# hw2.net
KiCad netlist of a schematic drawn in EAGLE
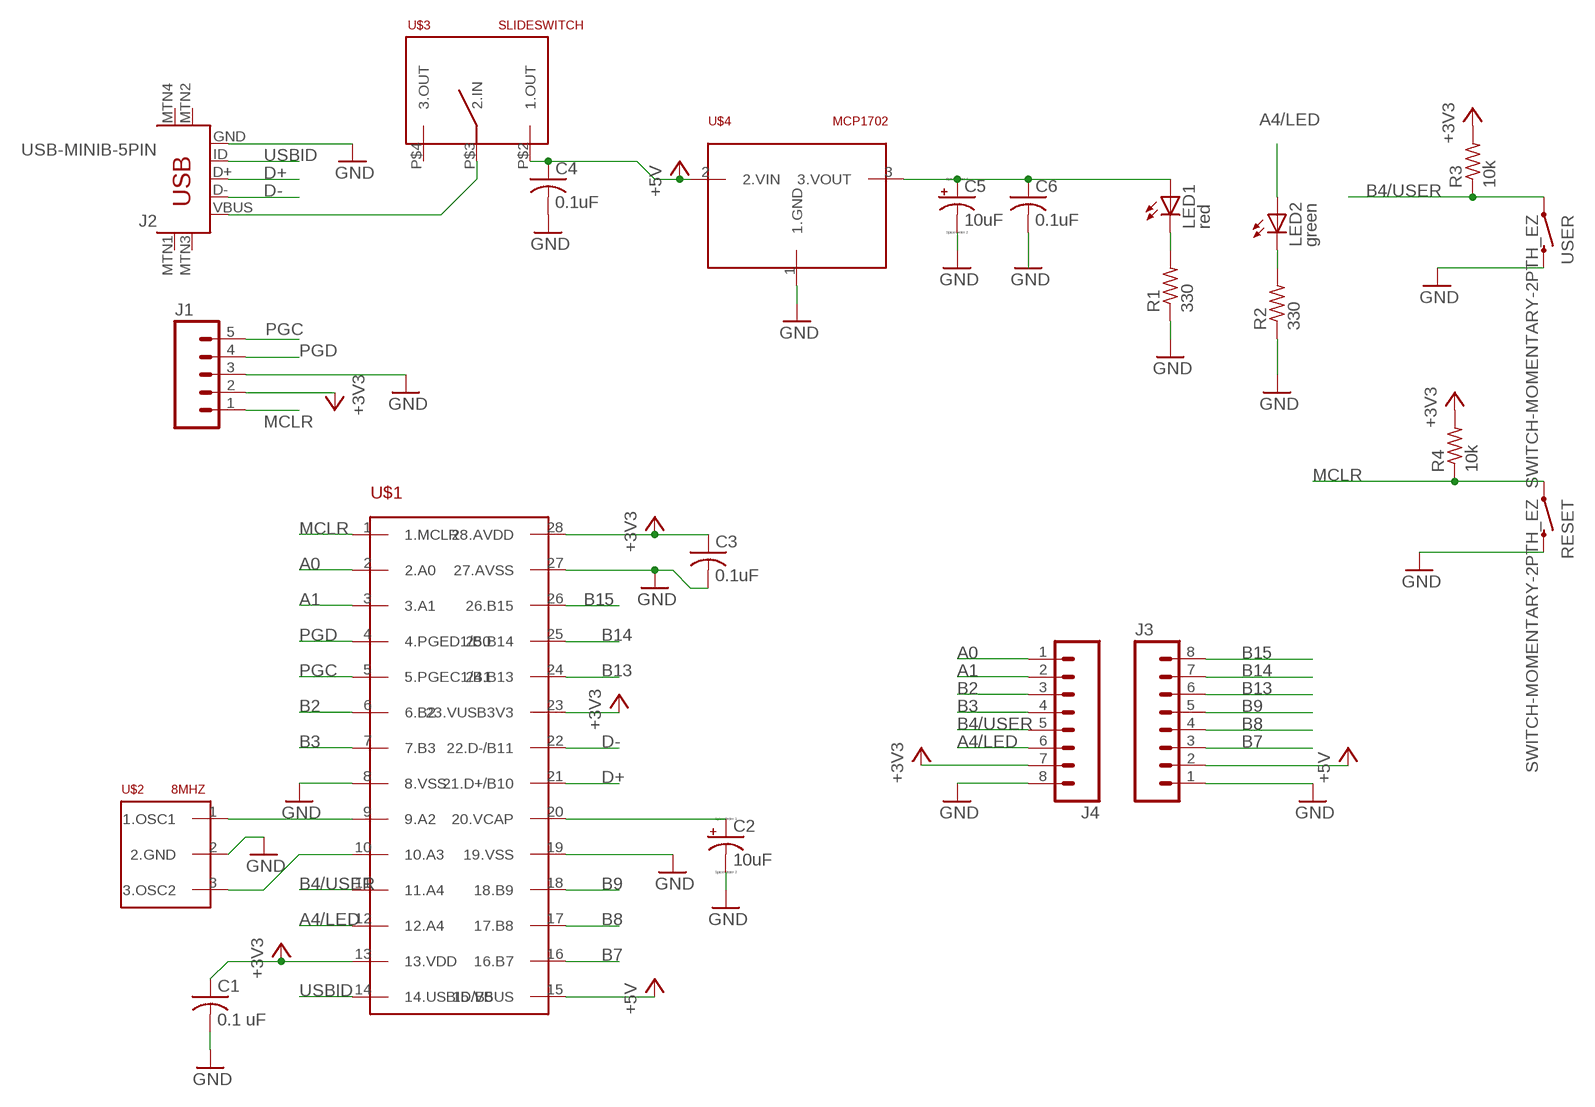
[diagram p0: schematic, sheet 1]

(export (version "E")
  (design (tool "Eeschema 10.0.6"))
  (components
    (comp (ref "C1")
      (value "0.1 uF")
      (footprint "eagle-import:C025-024X044")
      (libsource (lib "eagle-import") (part "C-US025-024X044"))
    )
    (comp (ref "C2")
      (value "10uF")
      (footprint "eagle-import:085CS_1AR")
      (libsource (lib "eagle-import") (part "CPOL-US085CS-1AR"))
    )
    (comp (ref "C3")
      (value "0.1uF")
      (footprint "eagle-import:C025-024X044")
      (libsource (lib "eagle-import") (part "C-US025-024X044"))
    )
    (comp (ref "C4")
      (value "0.1uF")
      (footprint "eagle-import:C025-024X044")
      (libsource (lib "eagle-import") (part "C-US025-024X044"))
    )
    (comp (ref "C5")
      (value "10uF")
      (footprint "eagle-import:085CS_1AR")
      (libsource (lib "eagle-import") (part "CPOL-US085CS-1AR"))
    )
    (comp (ref "C6")
      (value "0.1uF")
      (footprint "eagle-import:C025-024X044")
      (libsource (lib "eagle-import") (part "C-US025-024X044"))
    )
    (comp (ref "J1")
      (value "M05PTH")
      (footprint "eagle-import:1X05")
      (libsource (lib "eagle-import") (part "M05PTH"))
    )
    (comp (ref "J2")
      (value "USB-MINIB-5PIN")
      (footprint "eagle-import:USB-MINIB")
      (libsource (lib "eagle-import") (part "USB-MINIB-5PIN"))
    )
    (comp (ref "J3")
      (value "M08")
      (footprint "eagle-import:1X08_ROUND")
      (libsource (lib "eagle-import") (part "M08"))
    )
    (comp (ref "J4")
      (value "M08")
      (footprint "eagle-import:1X08_ROUND")
      (libsource (lib "eagle-import") (part "M08"))
    )
    (comp (ref "LED1")
      (value "red")
      (footprint "eagle-import:LED3MM")
      (libsource (lib "eagle-import") (part "LED3MM"))
    )
    (comp (ref "LED2")
      (value "green")
      (footprint "eagle-import:LED3MM")
      (libsource (lib "eagle-import") (part "LED3MM"))
    )
    (comp (ref "R1")
      (value "330")
      (footprint "eagle-import:0207_10")
      (libsource (lib "eagle-import") (part "R-US_0207/10"))
    )
    (comp (ref "R2")
      (value "330")
      (footprint "eagle-import:0207_10")
      (libsource (lib "eagle-import") (part "R-US_0207/10"))
    )
    (comp (ref "R3")
      (value "10k")
      (footprint "eagle-import:0207_10")
      (libsource (lib "eagle-import") (part "R-US_0207/10"))
    )
    (comp (ref "R4")
      (value "10k")
      (footprint "eagle-import:0207_10")
      (libsource (lib "eagle-import") (part "R-US_0207/10"))
    )
    (comp (ref "RESET")
      (value "SWITCH-MOMENTARY-2PTH_EZ")
      (footprint "eagle-import:TACTILE-PTH-EZ")
      (libsource (lib "eagle-import") (part "SWITCH-MOMENTARY-2PTH_EZ"))
    )
    (comp (ref "U$1")
      (value "PIC32MX250F128B")
      (footprint "eagle-import:DIL28-3")
      (libsource (lib "eagle-import") (part "PIC32MX250F128B"))
    )
    (comp (ref "U$2")
      (value "8MHZ")
      (footprint "eagle-import:RESONATOR-PTH")
      (libsource (lib "eagle-import") (part "8MHZ"))
    )
    (comp (ref "U$3")
      (value "SLIDESWITCH")
      (footprint "eagle-import:SLIDESWITCH")
      (libsource (lib "eagle-import") (part "SLIDESWITCH"))
    )
    (comp (ref "U$4")
      (value "MCP1702")
      (footprint "eagle-import:TO92")
      (libsource (lib "eagle-import") (part "MCP1702"))
    )
    (comp (ref "USER")
      (value "SWITCH-MOMENTARY-2PTH_EZ")
      (footprint "eagle-import:TACTILE-PTH-EZ")
      (libsource (lib "eagle-import") (part "SWITCH-MOMENTARY-2PTH_EZ"))
    )
  )
  (nets
    (net (code "1") (name "+3V3") (class "Default")
      (node (ref "C1") (pin "1") (pinfunction "1_1") (pintype "passive"))
      (node (ref "C3") (pin "1") (pinfunction "1_1") (pintype "passive"))
      (node (ref "J1") (pin "2") (pinfunction "2_2") (pintype "passive"))
      (node (ref "J4") (pin "7") (pinfunction "7_7") (pintype "passive"))
      (node (ref "R3") (pin "2") (pinfunction "2_2") (pintype "passive"))
      (node (ref "R4") (pin "2") (pinfunction "2_2") (pintype "passive"))
      (node (ref "U$1") (pin "13") (pinfunction "13.VDD_13") (pintype "bidirectional"))
      (node (ref "U$1") (pin "23") (pinfunction "23.VUSB3V3_23") (pintype "bidirectional"))
      (node (ref "U$1") (pin "28") (pinfunction "28.AVDD_28") (pintype "bidirectional"))
    )
    (net (code "2") (name "+5V") (class "Default")
      (node (ref "C4") (pin "1") (pinfunction "1_1") (pintype "passive"))
      (node (ref "J3") (pin "2") (pinfunction "2_2") (pintype "passive"))
      (node (ref "U$1") (pin "15") (pinfunction "15.VBUS_15") (pintype "bidirectional"))
      (node (ref "U$3") (pin "P$2") (pinfunction "1.OUT_P$2") (pintype "bidirectional"))
      (node (ref "U$4") (pin "2") (pinfunction "2.VIN_2") (pintype "bidirectional"))
    )
    (net (code "3") (name "/A0") (class "Default")
      (node (ref "J4") (pin "1") (pinfunction "1_1") (pintype "passive"))
      (node (ref "U$1") (pin "2") (pinfunction "2.A0_2") (pintype "bidirectional"))
    )
    (net (code "4") (name "/A1") (class "Default")
      (node (ref "J4") (pin "2") (pinfunction "2_2") (pintype "passive"))
      (node (ref "U$1") (pin "3") (pinfunction "3.A1_3") (pintype "bidirectional"))
    )
    (net (code "5") (name "/A4{slash}LED") (class "Default")
      (node (ref "J4") (pin "6") (pinfunction "6_6") (pintype "passive"))
      (node (ref "LED2") (pin "A") (pinfunction "A_A") (pintype "passive"))
      (node (ref "U$1") (pin "12") (pinfunction "12.A4_12") (pintype "bidirectional"))
    )
    (net (code "6") (name "/B2") (class "Default")
      (node (ref "J4") (pin "3") (pinfunction "3_3") (pintype "passive"))
      (node (ref "U$1") (pin "6") (pinfunction "6.B2_6") (pintype "bidirectional"))
    )
    (net (code "7") (name "/B3") (class "Default")
      (node (ref "J4") (pin "4") (pinfunction "4_4") (pintype "passive"))
      (node (ref "U$1") (pin "7") (pinfunction "7.B3_7") (pintype "bidirectional"))
    )
    (net (code "8") (name "/B4{slash}USER") (class "Default")
      (node (ref "J4") (pin "5") (pinfunction "5_5") (pintype "passive"))
      (node (ref "R3") (pin "1") (pinfunction "1_1") (pintype "passive"))
      (node (ref "U$1") (pin "11") (pinfunction "11.A4_11") (pintype "bidirectional"))
      (node (ref "USER") (pin "1") (pinfunction "1_1") (pintype "passive"))
    )
    (net (code "9") (name "/B7") (class "Default")
      (node (ref "J3") (pin "3") (pinfunction "3_3") (pintype "passive"))
      (node (ref "U$1") (pin "16") (pinfunction "16.B7_16") (pintype "bidirectional"))
    )
    (net (code "10") (name "/B8") (class "Default")
      (node (ref "J3") (pin "4") (pinfunction "4_4") (pintype "passive"))
      (node (ref "U$1") (pin "17") (pinfunction "17.B8_17") (pintype "bidirectional"))
    )
    (net (code "11") (name "/B9") (class "Default")
      (node (ref "J3") (pin "5") (pinfunction "5_5") (pintype "passive"))
      (node (ref "U$1") (pin "18") (pinfunction "18.B9_18") (pintype "bidirectional"))
    )
    (net (code "12") (name "/B13") (class "Default")
      (node (ref "J3") (pin "6") (pinfunction "6_6") (pintype "passive"))
      (node (ref "U$1") (pin "24") (pinfunction "24.B13_24") (pintype "bidirectional"))
    )
    (net (code "13") (name "/B14") (class "Default")
      (node (ref "J3") (pin "7") (pinfunction "7_7") (pintype "passive"))
      (node (ref "U$1") (pin "25") (pinfunction "25.B14_25") (pintype "bidirectional"))
    )
    (net (code "14") (name "/B15") (class "Default")
      (node (ref "J3") (pin "8") (pinfunction "8_8") (pintype "passive"))
      (node (ref "U$1") (pin "26") (pinfunction "26.B15_26") (pintype "bidirectional"))
    )
    (net (code "15") (name "/D+") (class "Default")
      (node (ref "J2") (pin "D+") (pinfunction "D+_D+") (pintype "bidirectional"))
      (node (ref "U$1") (pin "21") (pinfunction "21.D+/B10_21") (pintype "bidirectional"))
    )
    (net (code "16") (name "/D-") (class "Default")
      (node (ref "J2") (pin "D-") (pinfunction "D-_D-") (pintype "bidirectional"))
      (node (ref "U$1") (pin "22") (pinfunction "22.D-/B11_22") (pintype "bidirectional"))
    )
    (net (code "17") (name "/MCLR") (class "Default")
      (node (ref "J1") (pin "1") (pinfunction "1_1") (pintype "passive"))
      (node (ref "R4") (pin "1") (pinfunction "1_1") (pintype "passive"))
      (node (ref "RESET") (pin "1") (pinfunction "1_1") (pintype "passive"))
      (node (ref "U$1") (pin "1") (pinfunction "1.MCLR_1") (pintype "bidirectional"))
    )
    (net (code "18") (name "/PGC") (class "Default")
      (node (ref "J1") (pin "5") (pinfunction "5_5") (pintype "passive"))
      (node (ref "U$1") (pin "5") (pinfunction "5.PGEC1/B1_5") (pintype "bidirectional"))
    )
    (net (code "19") (name "/PGD") (class "Default")
      (node (ref "J1") (pin "4") (pinfunction "4_4") (pintype "passive"))
      (node (ref "U$1") (pin "4") (pinfunction "4.PGED1/B0_4") (pintype "bidirectional"))
    )
    (net (code "20") (name "/USBID") (class "Default")
      (node (ref "J2") (pin "ID") (pinfunction "ID_ID") (pintype "bidirectional"))
      (node (ref "U$1") (pin "14") (pinfunction "14.USBID/B5_14") (pintype "bidirectional"))
    )
    (net (code "21") (name "GND") (class "Default")
      (node (ref "C1") (pin "2") (pinfunction "2_2") (pintype "passive"))
      (node (ref "C2") (pin "-") (pinfunction "-_-") (pintype "passive"))
      (node (ref "C3") (pin "2") (pinfunction "2_2") (pintype "passive"))
      (node (ref "C4") (pin "2") (pinfunction "2_2") (pintype "passive"))
      (node (ref "C5") (pin "-") (pinfunction "-_-") (pintype "passive"))
      (node (ref "J1") (pin "3") (pinfunction "3_3") (pintype "passive"))
      (node (ref "J2") (pin "GND") (pinfunction "GND_GND") (pintype "bidirectional"))
      (node (ref "J3") (pin "1") (pinfunction "1_1") (pintype "passive"))
      (node (ref "J4") (pin "8") (pinfunction "8_8") (pintype "passive"))
      (node (ref "R1") (pin "1") (pinfunction "1_1") (pintype "passive"))
      (node (ref "R2") (pin "1") (pinfunction "1_1") (pintype "passive"))
      (node (ref "RESET") (pin "3") (pinfunction "2_3") (pintype "passive"))
      (node (ref "U$1") (pin "19") (pinfunction "19.VSS_19") (pintype "bidirectional"))
      (node (ref "U$1") (pin "27") (pinfunction "27.AVSS_27") (pintype "bidirectional"))
      (node (ref "U$1") (pin "8") (pinfunction "8.VSS_8") (pintype "bidirectional"))
      (node (ref "U$2") (pin "2") (pinfunction "2.GND_2") (pintype "bidirectional"))
      (node (ref "U$4") (pin "1") (pinfunction "1.GND_1") (pintype "bidirectional"))
      (node (ref "USER") (pin "3") (pinfunction "2_3") (pintype "passive"))
    )
    (net (code "22") (name "Net-(LED1-C)") (class "Default")
      (node (ref "LED1") (pin "K") (pinfunction "C_K") (pintype "passive"))
      (node (ref "R1") (pin "2") (pinfunction "2_2") (pintype "passive"))
    )
    (net (code "23") (name "Net-(LED2-C)") (class "Default")
      (node (ref "LED2") (pin "K") (pinfunction "C_K") (pintype "passive"))
      (node (ref "R2") (pin "2") (pinfunction "2_2") (pintype "passive"))
    )
    (net (code "24") (name "Net-(U$1-9.A2)") (class "Default")
      (node (ref "U$1") (pin "9") (pinfunction "9.A2_9") (pintype "bidirectional"))
      (node (ref "U$2") (pin "1") (pinfunction "1.OSC1_1") (pintype "bidirectional"))
    )
    (net (code "25") (name "Net-(U$1-10.A3)") (class "Default")
      (node (ref "U$1") (pin "10") (pinfunction "10.A3_10") (pintype "bidirectional"))
      (node (ref "U$2") (pin "3") (pinfunction "3.OSC2_3") (pintype "bidirectional"))
    )
    (net (code "26") (name "Net-(U$1-20.VCAP)") (class "Default")
      (node (ref "C2") (pin "+") (pinfunction "+_+") (pintype "passive"))
      (node (ref "U$1") (pin "20") (pinfunction "20.VCAP_20") (pintype "bidirectional"))
    )
    (net (code "27") (name "Net-(U$3-2.IN)") (class "Default")
      (node (ref "J2") (pin "VBUS") (pinfunction "VBUS_VBUS") (pintype "bidirectional"))
      (node (ref "U$3") (pin "P$3") (pinfunction "2.IN_P$3") (pintype "bidirectional"))
    )
    (net (code "28") (name "Net-(U$4-3.VOUT)") (class "Default")
      (node (ref "C5") (pin "+") (pinfunction "+_+") (pintype "passive"))
      (node (ref "C6") (pin "1") (pinfunction "1_1") (pintype "passive"))
      (node (ref "LED1") (pin "A") (pinfunction "A_A") (pintype "passive"))
      (node (ref "U$4") (pin "3") (pinfunction "3.VOUT_3") (pintype "bidirectional"))
    )
    (net (code "29") (name "unconnected-(C6-Pad2)") (class "Default")
      (node (ref "C6") (pin "2") (pinfunction "2_2") (pintype "passive"))
    )
    (net (code "30") (name "unconnected-(J2-MTN1-PadMTN3)") (class "Default")
      (node (ref "J2") (pin "MTN3") (pinfunction "MTN1_MTN3") (pintype "bidirectional"))
    )
    (net (code "31") (name "unconnected-(J2-MTN2-PadMTN1)") (class "Default")
      (node (ref "J2") (pin "MTN1") (pinfunction "MTN2_MTN1") (pintype "bidirectional"))
    )
    (net (code "32") (name "unconnected-(J2-MTN3-PadMTN2)") (class "Default")
      (node (ref "J2") (pin "MTN2") (pinfunction "MTN3_MTN2") (pintype "bidirectional"))
    )
    (net (code "33") (name "unconnected-(J2-PadMTN4)") (class "Default")
      (node (ref "J2") (pin "MTN4") (pinfunction "MTN4_MTN4") (pintype "bidirectional"))
    )
    (net (code "34") (name "unconnected-(U$3-3.OUT-PadP$4)") (class "Default")
      (node (ref "U$3") (pin "P$4") (pinfunction "3.OUT_P$4") (pintype "bidirectional"))
    )
  )
)
